# m1-ram.net
KiCad netlist of a schematic drawn in EAGLE
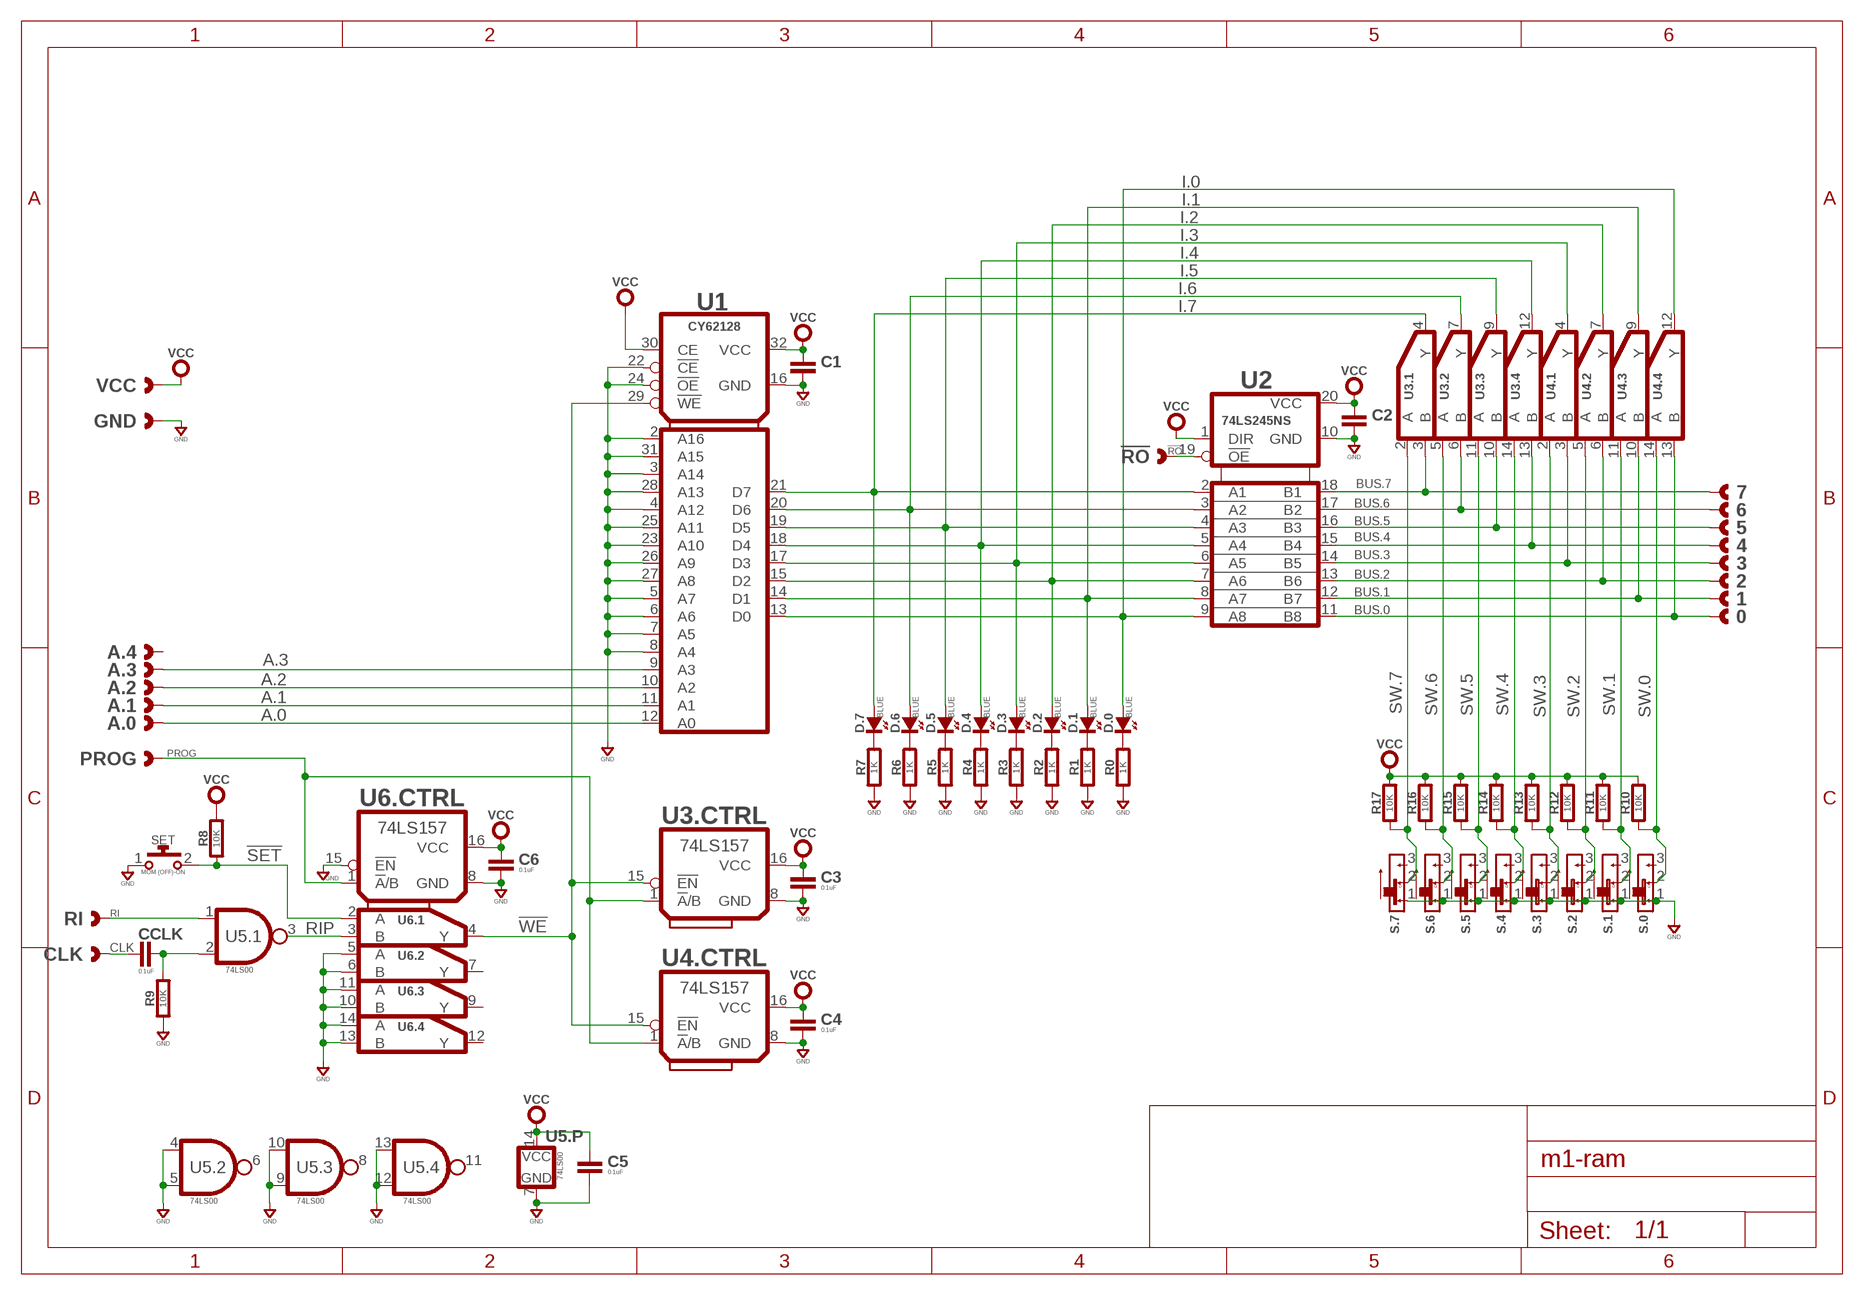
[diagram p0: schematic, sheet 1]

(export (version "E")
  (design (tool "Eeschema 10.0.6"))
  (components
    (comp (ref "!RO")
      (value "CAST-01X1")
      (footprint "eagle-import:CAST01-2.54MM")
      (libsource (lib "eagle-import") (part "CAST-01X1"))
    )
    (comp (ref "0")
      (value "CAST-01X1")
      (footprint "eagle-import:CAST01-2.54MM")
      (libsource (lib "eagle-import") (part "CAST-01X1"))
    )
    (comp (ref "1")
      (value "CAST-01X1")
      (footprint "eagle-import:CAST01-2.54MM")
      (libsource (lib "eagle-import") (part "CAST-01X1"))
    )
    (comp (ref "2")
      (value "CAST-01X1")
      (footprint "eagle-import:CAST01-2.54MM")
      (libsource (lib "eagle-import") (part "CAST-01X1"))
    )
    (comp (ref "3")
      (value "CAST-01X1")
      (footprint "eagle-import:CAST01-2.54MM")
      (libsource (lib "eagle-import") (part "CAST-01X1"))
    )
    (comp (ref "4")
      (value "CAST-01X1")
      (footprint "eagle-import:CAST01-2.54MM")
      (libsource (lib "eagle-import") (part "CAST-01X1"))
    )
    (comp (ref "5")
      (value "CAST-01X1")
      (footprint "eagle-import:CAST01-2.54MM")
      (libsource (lib "eagle-import") (part "CAST-01X1"))
    )
    (comp (ref "6")
      (value "CAST-01X1")
      (footprint "eagle-import:CAST01-2.54MM")
      (libsource (lib "eagle-import") (part "CAST-01X1"))
    )
    (comp (ref "7")
      (value "CAST-01X1")
      (footprint "eagle-import:CAST01-2.54MM")
      (libsource (lib "eagle-import") (part "CAST-01X1"))
    )
    (comp (ref "A.0")
      (value "CAST-01X1")
      (footprint "eagle-import:CAST01-2.54MM")
      (libsource (lib "eagle-import") (part "CAST-01X1"))
    )
    (comp (ref "A.1")
      (value "CAST-01X1")
      (footprint "eagle-import:CAST01-2.54MM")
      (libsource (lib "eagle-import") (part "CAST-01X1"))
    )
    (comp (ref "A.2")
      (value "CAST-01X1")
      (footprint "eagle-import:CAST01-2.54MM")
      (libsource (lib "eagle-import") (part "CAST-01X1"))
    )
    (comp (ref "A.3")
      (value "CAST-01X1")
      (footprint "eagle-import:CAST01-2.54MM")
      (libsource (lib "eagle-import") (part "CAST-01X1"))
    )
    (comp (ref "A.4")
      (value "CAST-01X1")
      (footprint "eagle-import:CAST01-2.54MM")
      (libsource (lib "eagle-import") (part "CAST-01X1"))
    )
    (comp (ref "C1")
      (value "CAPACITOR0603")
      (footprint "eagle-import:0603-CAP")
      (libsource (lib "eagle-import") (part "CAPACITOR0603"))
    )
    (comp (ref "C2")
      (value "CAPACITOR0603")
      (footprint "eagle-import:0603-CAP")
      (libsource (lib "eagle-import") (part "CAPACITOR0603"))
    )
    (comp (ref "C3")
      (value "0.1uF")
      (footprint "eagle-import:0603-CAP")
      (libsource (lib "eagle-import") (part "CAPACITOR0603"))
    )
    (comp (ref "C4")
      (value "0.1uF")
      (footprint "eagle-import:0603-CAP")
      (libsource (lib "eagle-import") (part "CAPACITOR0603"))
    )
    (comp (ref "C5")
      (value "0.1uF")
      (footprint "eagle-import:0603-CAP")
      (libsource (lib "eagle-import") (part "CAPACITOR0603"))
    )
    (comp (ref "C6")
      (value "0.1uF")
      (footprint "eagle-import:0603-CAP")
      (libsource (lib "eagle-import") (part "CAPACITOR0603"))
    )
    (comp (ref "CCLK")
      (value "0.1uF")
      (footprint "eagle-import:0603-CAP")
      (libsource (lib "eagle-import") (part "CAPACITOR0603"))
    )
    (comp (ref "CLK")
      (value "CAST-01X1")
      (footprint "eagle-import:CAST01-2.54MM")
      (libsource (lib "eagle-import") (part "CAST-01X1"))
    )
    (comp (ref "D.0")
      (value "BLUE")
      (footprint "eagle-import:SMD_0603")
      (libsource (lib "eagle-import") (part "SMT0603"))
    )
    (comp (ref "D.1")
      (value "BLUE")
      (footprint "eagle-import:SMD_0603")
      (libsource (lib "eagle-import") (part "SMT0603"))
    )
    (comp (ref "D.2")
      (value "BLUE")
      (footprint "eagle-import:SMD_0603")
      (libsource (lib "eagle-import") (part "SMT0603"))
    )
    (comp (ref "D.3")
      (value "BLUE")
      (footprint "eagle-import:SMD_0603")
      (libsource (lib "eagle-import") (part "SMT0603"))
    )
    (comp (ref "D.4")
      (value "BLUE")
      (footprint "eagle-import:SMD_0603")
      (libsource (lib "eagle-import") (part "SMT0603"))
    )
    (comp (ref "D.5")
      (value "BLUE")
      (footprint "eagle-import:SMD_0603")
      (libsource (lib "eagle-import") (part "SMT0603"))
    )
    (comp (ref "D.6")
      (value "BLUE")
      (footprint "eagle-import:SMD_0603")
      (libsource (lib "eagle-import") (part "SMT0603"))
    )
    (comp (ref "D.7")
      (value "BLUE")
      (footprint "eagle-import:SMD_0603")
      (libsource (lib "eagle-import") (part "SMT0603"))
    )
    (comp (ref "GND")
      (value "CAST-01X1")
      (footprint "eagle-import:CAST01-2.54MM")
      (libsource (lib "eagle-import") (part "CAST-01X1"))
    )
    (comp (ref "PROG")
      (value "CAST-01X1")
      (footprint "eagle-import:CAST01-2.54MM")
      (libsource (lib "eagle-import") (part "CAST-01X1"))
    )
    (comp (ref "R0")
      (value "1K")
      (footprint "eagle-import:0603-RES")
      (libsource (lib "eagle-import") (part "RESISTOR0603"))
    )
    (comp (ref "R1")
      (value "1K")
      (footprint "eagle-import:0603-RES")
      (libsource (lib "eagle-import") (part "RESISTOR0603"))
    )
    (comp (ref "R2")
      (value "1K")
      (footprint "eagle-import:0603-RES")
      (libsource (lib "eagle-import") (part "RESISTOR0603"))
    )
    (comp (ref "R3")
      (value "1K")
      (footprint "eagle-import:0603-RES")
      (libsource (lib "eagle-import") (part "RESISTOR0603"))
    )
    (comp (ref "R4")
      (value "1K")
      (footprint "eagle-import:0603-RES")
      (libsource (lib "eagle-import") (part "RESISTOR0603"))
    )
    (comp (ref "R5")
      (value "1K")
      (footprint "eagle-import:0603-RES")
      (libsource (lib "eagle-import") (part "RESISTOR0603"))
    )
    (comp (ref "R6")
      (value "1K")
      (footprint "eagle-import:0603-RES")
      (libsource (lib "eagle-import") (part "RESISTOR0603"))
    )
    (comp (ref "R7")
      (value "1K")
      (footprint "eagle-import:0603-RES")
      (libsource (lib "eagle-import") (part "RESISTOR0603"))
    )
    (comp (ref "R8")
      (value "10K")
      (footprint "eagle-import:0603-RES")
      (libsource (lib "eagle-import") (part "RESISTOR0603"))
    )
    (comp (ref "R9")
      (value "10K")
      (footprint "eagle-import:0603-RES")
      (libsource (lib "eagle-import") (part "RESISTOR0603"))
    )
    (comp (ref "R10")
      (value "10K")
      (footprint "eagle-import:0603-RES")
      (libsource (lib "eagle-import") (part "RESISTOR0603"))
    )
    (comp (ref "R11")
      (value "10K")
      (footprint "eagle-import:0603-RES")
      (libsource (lib "eagle-import") (part "RESISTOR0603"))
    )
    (comp (ref "R12")
      (value "10K")
      (footprint "eagle-import:0603-RES")
      (libsource (lib "eagle-import") (part "RESISTOR0603"))
    )
    (comp (ref "R13")
      (value "10K")
      (footprint "eagle-import:0603-RES")
      (libsource (lib "eagle-import") (part "RESISTOR0603"))
    )
    (comp (ref "R14")
      (value "10K")
      (footprint "eagle-import:0603-RES")
      (libsource (lib "eagle-import") (part "RESISTOR0603"))
    )
    (comp (ref "R15")
      (value "10K")
      (footprint "eagle-import:0603-RES")
      (libsource (lib "eagle-import") (part "RESISTOR0603"))
    )
    (comp (ref "R16")
      (value "10K")
      (footprint "eagle-import:0603-RES")
      (libsource (lib "eagle-import") (part "RESISTOR0603"))
    )
    (comp (ref "R17")
      (value "10K")
      (footprint "eagle-import:0603-RES")
      (libsource (lib "eagle-import") (part "RESISTOR0603"))
    )
    (comp (ref "RI")
      (value "CAST-01X1")
      (footprint "eagle-import:CAST01-2.54MM")
      (libsource (lib "eagle-import") (part "CAST-01X1"))
    )
    (comp (ref "S.0")
      (value "SLIDE-SPDTJS102011JCQN")
      (footprint "eagle-import:CK_JS102011JCQN")
      (libsource (lib "eagle-import") (part "SLIDE-SPDTJS102011JCQN"))
    )
    (comp (ref "S.1")
      (value "SLIDE-SPDTJS102011JCQN")
      (footprint "eagle-import:CK_JS102011JCQN")
      (libsource (lib "eagle-import") (part "SLIDE-SPDTJS102011JCQN"))
    )
    (comp (ref "S.2")
      (value "SLIDE-SPDTJS102011JCQN")
      (footprint "eagle-import:CK_JS102011JCQN")
      (libsource (lib "eagle-import") (part "SLIDE-SPDTJS102011JCQN"))
    )
    (comp (ref "S.3")
      (value "SLIDE-SPDTJS102011JCQN")
      (footprint "eagle-import:CK_JS102011JCQN")
      (libsource (lib "eagle-import") (part "SLIDE-SPDTJS102011JCQN"))
    )
    (comp (ref "S.4")
      (value "SLIDE-SPDTJS102011JCQN")
      (footprint "eagle-import:CK_JS102011JCQN")
      (libsource (lib "eagle-import") (part "SLIDE-SPDTJS102011JCQN"))
    )
    (comp (ref "S.5")
      (value "SLIDE-SPDTJS102011JCQN")
      (footprint "eagle-import:CK_JS102011JCQN")
      (libsource (lib "eagle-import") (part "SLIDE-SPDTJS102011JCQN"))
    )
    (comp (ref "S.6")
      (value "SLIDE-SPDTJS102011JCQN")
      (footprint "eagle-import:CK_JS102011JCQN")
      (libsource (lib "eagle-import") (part "SLIDE-SPDTJS102011JCQN"))
    )
    (comp (ref "S.7")
      (value "SLIDE-SPDTJS102011JCQN")
      (footprint "eagle-import:CK_JS102011JCQN")
      (libsource (lib "eagle-import") (part "SLIDE-SPDTJS102011JCQN"))
    )
    (comp (ref "SET")
      (value "MOM (OFF)-ON")
      (footprint "eagle-import:SWITCH-0635-2P-SMD")
      (fields (field (name "MFR") "CK Switch") (field (name "MPN") "PTS635S*SMTR"))
      (libsource (lib "eagle-import") (part "TACTILE-2PSMD"))
    )
    (comp (ref "U1")
      (value "CY62128")
      (footprint "eagle-import:SO32")
      (fields (field (name "MFR") "Cypress") (field (name "MPN") "CY62128ELL-45SXI"))
      (libsource (lib "eagle-import") (part "SRAM_128KX8CYPRESS"))
    )
    (comp (ref "U2")
      (value "74LS245NS")
      (footprint "eagle-import:SO20")
      (libsource (lib "eagle-import") (part "74245?NSLS"))
    )
    (comp (ref "U3")
      (value "74LS157")
      (footprint "eagle-import:SO16")
      (fields (field (name "MPN") "74LS157D"))
      (libsource (lib "eagle-import") (part "74157?DLS"))
    )
    (comp (ref "U4")
      (value "74LS157")
      (footprint "eagle-import:SO16")
      (fields (field (name "MPN") "74LS157D"))
      (libsource (lib "eagle-import") (part "74157?DLS"))
    )
    (comp (ref "U5")
      (value "74LS00")
      (footprint "eagle-import:SOP14")
      (fields (field (name "MPN") "74LS00N"))
      (libsource (lib "eagle-import") (part "7400?DLS"))
    )
    (comp (ref "U6")
      (value "74LS157")
      (footprint "eagle-import:SO16")
      (fields (field (name "MPN") "74LS157D"))
      (libsource (lib "eagle-import") (part "74157?DLS"))
    )
    (comp (ref "VCC")
      (value "CAST-01X1")
      (footprint "eagle-import:CAST01-2.54MM")
      (libsource (lib "eagle-import") (part "CAST-01X1"))
    )
  )
  (nets
    (net (code "1") (name "/A.0") (class "Default")
      (node (ref "A.0") (pin "1") (pinfunction "1_1") (pintype "bidirectional"))
      (node (ref "U1") (pin "12") (pinfunction "A0_12") (pintype "input"))
    )
    (net (code "2") (name "/A.1") (class "Default")
      (node (ref "A.1") (pin "1") (pinfunction "1_1") (pintype "bidirectional"))
      (node (ref "U1") (pin "11") (pinfunction "A1_11") (pintype "input"))
    )
    (net (code "3") (name "/A.2") (class "Default")
      (node (ref "A.2") (pin "1") (pinfunction "1_1") (pintype "bidirectional"))
      (node (ref "U1") (pin "10") (pinfunction "A2_10") (pintype "input"))
    )
    (net (code "4") (name "/A.3") (class "Default")
      (node (ref "A.3") (pin "1") (pinfunction "1_1") (pintype "bidirectional"))
      (node (ref "U1") (pin "9") (pinfunction "A3_9") (pintype "input"))
    )
    (net (code "5") (name "/BUS.0") (class "Default")
      (node (ref "0") (pin "1") (pinfunction "1_1") (pintype "bidirectional"))
      (node (ref "U2") (pin "11") (pinfunction "B8_11") (pintype "bidirectional"))
      (node (ref "U4") (pin "13") (pinfunction "B_13") (pintype "input"))
    )
    (net (code "6") (name "/BUS.1") (class "Default")
      (node (ref "1") (pin "1") (pinfunction "1_1") (pintype "bidirectional"))
      (node (ref "U2") (pin "12") (pinfunction "B7_12") (pintype "bidirectional"))
      (node (ref "U4") (pin "10") (pinfunction "B_10") (pintype "input"))
    )
    (net (code "7") (name "/BUS.2") (class "Default")
      (node (ref "2") (pin "1") (pinfunction "1_1") (pintype "bidirectional"))
      (node (ref "U2") (pin "13") (pinfunction "B6_13") (pintype "bidirectional"))
      (node (ref "U4") (pin "6") (pinfunction "B_6") (pintype "input"))
    )
    (net (code "8") (name "/BUS.3") (class "Default")
      (node (ref "3") (pin "1") (pinfunction "1_1") (pintype "bidirectional"))
      (node (ref "U2") (pin "14") (pinfunction "B5_14") (pintype "bidirectional"))
      (node (ref "U4") (pin "3") (pinfunction "B_3") (pintype "input"))
    )
    (net (code "9") (name "/BUS.4") (class "Default")
      (node (ref "4") (pin "1") (pinfunction "1_1") (pintype "bidirectional"))
      (node (ref "U2") (pin "15") (pinfunction "B4_15") (pintype "bidirectional"))
      (node (ref "U3") (pin "13") (pinfunction "B_13") (pintype "input"))
    )
    (net (code "10") (name "/BUS.5") (class "Default")
      (node (ref "5") (pin "1") (pinfunction "1_1") (pintype "bidirectional"))
      (node (ref "U2") (pin "16") (pinfunction "B3_16") (pintype "bidirectional"))
      (node (ref "U3") (pin "10") (pinfunction "B_10") (pintype "input"))
    )
    (net (code "11") (name "/BUS.6") (class "Default")
      (node (ref "6") (pin "1") (pinfunction "1_1") (pintype "bidirectional"))
      (node (ref "U2") (pin "17") (pinfunction "B2_17") (pintype "bidirectional"))
      (node (ref "U3") (pin "6") (pinfunction "B_6") (pintype "input"))
    )
    (net (code "12") (name "/BUS.7") (class "Default")
      (node (ref "7") (pin "1") (pinfunction "1_1") (pintype "bidirectional"))
      (node (ref "U2") (pin "18") (pinfunction "B1_18") (pintype "bidirectional"))
      (node (ref "U3") (pin "3") (pinfunction "B_3") (pintype "input"))
    )
    (net (code "13") (name "/CLK") (class "Default")
      (node (ref "CCLK") (pin "1") (pinfunction "1_1") (pintype "passive"))
      (node (ref "CLK") (pin "1") (pinfunction "1_1") (pintype "bidirectional"))
    )
    (net (code "14") (name "/I.0") (class "Default")
      (node (ref "D.0") (pin "A") (pinfunction "A_A") (pintype "passive"))
      (node (ref "U1") (pin "13") (pinfunction "D0_13") (pintype "bidirectional"))
      (node (ref "U2") (pin "9") (pinfunction "A8_9") (pintype "bidirectional"))
      (node (ref "U4") (pin "12") (pinfunction "Y_12") (pintype "output"))
    )
    (net (code "15") (name "/I.1") (class "Default")
      (node (ref "D.1") (pin "A") (pinfunction "A_A") (pintype "passive"))
      (node (ref "U1") (pin "14") (pinfunction "D1_14") (pintype "bidirectional"))
      (node (ref "U2") (pin "8") (pinfunction "A7_8") (pintype "bidirectional"))
      (node (ref "U4") (pin "9") (pinfunction "Y_9") (pintype "output"))
    )
    (net (code "16") (name "/I.2") (class "Default")
      (node (ref "D.2") (pin "A") (pinfunction "A_A") (pintype "passive"))
      (node (ref "U1") (pin "15") (pinfunction "D2_15") (pintype "bidirectional"))
      (node (ref "U2") (pin "7") (pinfunction "A6_7") (pintype "bidirectional"))
      (node (ref "U4") (pin "7") (pinfunction "Y_7") (pintype "output"))
    )
    (net (code "17") (name "/I.3") (class "Default")
      (node (ref "D.3") (pin "A") (pinfunction "A_A") (pintype "passive"))
      (node (ref "U1") (pin "17") (pinfunction "D3_17") (pintype "bidirectional"))
      (node (ref "U2") (pin "6") (pinfunction "A5_6") (pintype "bidirectional"))
      (node (ref "U4") (pin "4") (pinfunction "Y_4") (pintype "output"))
    )
    (net (code "18") (name "/I.4") (class "Default")
      (node (ref "D.4") (pin "A") (pinfunction "A_A") (pintype "passive"))
      (node (ref "U1") (pin "18") (pinfunction "D4_18") (pintype "bidirectional"))
      (node (ref "U2") (pin "5") (pinfunction "A4_5") (pintype "bidirectional"))
      (node (ref "U3") (pin "12") (pinfunction "Y_12") (pintype "output"))
    )
    (net (code "19") (name "/I.5") (class "Default")
      (node (ref "D.5") (pin "A") (pinfunction "A_A") (pintype "passive"))
      (node (ref "U1") (pin "19") (pinfunction "D5_19") (pintype "bidirectional"))
      (node (ref "U2") (pin "4") (pinfunction "A3_4") (pintype "bidirectional"))
      (node (ref "U3") (pin "9") (pinfunction "Y_9") (pintype "output"))
    )
    (net (code "20") (name "/I.6") (class "Default")
      (node (ref "D.6") (pin "A") (pinfunction "A_A") (pintype "passive"))
      (node (ref "U1") (pin "20") (pinfunction "D6_20") (pintype "bidirectional"))
      (node (ref "U2") (pin "3") (pinfunction "A2_3") (pintype "bidirectional"))
      (node (ref "U3") (pin "7") (pinfunction "Y_7") (pintype "output"))
    )
    (net (code "21") (name "/I.7") (class "Default")
      (node (ref "D.7") (pin "A") (pinfunction "A_A") (pintype "passive"))
      (node (ref "U1") (pin "21") (pinfunction "D7_21") (pintype "bidirectional"))
      (node (ref "U2") (pin "2") (pinfunction "A1_2") (pintype "bidirectional"))
      (node (ref "U3") (pin "4") (pinfunction "Y_4") (pintype "output"))
    )
    (net (code "22") (name "/PROG") (class "Default")
      (node (ref "PROG") (pin "1") (pinfunction "1_1") (pintype "bidirectional"))
      (node (ref "U3") (pin "1") (pinfunction "~{A}/B_1") (pintype "output"))
      (node (ref "U4") (pin "1") (pinfunction "~{A}/B_1") (pintype "output"))
      (node (ref "U6") (pin "1") (pinfunction "~{A}/B_1") (pintype "output"))
    )
    (net (code "23") (name "/RI") (class "Default")
      (node (ref "RI") (pin "1") (pinfunction "1_1") (pintype "bidirectional"))
      (node (ref "U5") (pin "1") (pinfunction "A_1") (pintype "input"))
    )
    (net (code "24") (name "/RIP") (class "Default")
      (node (ref "U5") (pin "3") (pinfunction "Y_3") (pintype "output"))
      (node (ref "U6") (pin "3") (pinfunction "B_3") (pintype "input"))
    )
    (net (code "25") (name "/SW.0") (class "Default")
      (node (ref "R10") (pin "1") (pinfunction "1_1") (pintype "passive"))
      (node (ref "S.0") (pin "2") (pinfunction "2_2") (pintype "bidirectional"))
      (node (ref "U4") (pin "14") (pinfunction "A_14") (pintype "input"))
    )
    (net (code "26") (name "/SW.1") (class "Default")
      (node (ref "R11") (pin "1") (pinfunction "1_1") (pintype "passive"))
      (node (ref "S.1") (pin "2") (pinfunction "2_2") (pintype "bidirectional"))
      (node (ref "U4") (pin "11") (pinfunction "A_11") (pintype "input"))
    )
    (net (code "27") (name "/SW.2") (class "Default")
      (node (ref "R12") (pin "1") (pinfunction "1_1") (pintype "passive"))
      (node (ref "S.2") (pin "2") (pinfunction "2_2") (pintype "bidirectional"))
      (node (ref "U4") (pin "5") (pinfunction "A_5") (pintype "input"))
    )
    (net (code "28") (name "/SW.3") (class "Default")
      (node (ref "R13") (pin "1") (pinfunction "1_1") (pintype "passive"))
      (node (ref "S.3") (pin "2") (pinfunction "2_2") (pintype "bidirectional"))
      (node (ref "U4") (pin "2") (pinfunction "A_2") (pintype "input"))
    )
    (net (code "29") (name "/SW.4") (class "Default")
      (node (ref "R14") (pin "1") (pinfunction "1_1") (pintype "passive"))
      (node (ref "S.4") (pin "2") (pinfunction "2_2") (pintype "bidirectional"))
      (node (ref "U3") (pin "14") (pinfunction "A_14") (pintype "input"))
    )
    (net (code "30") (name "/SW.5") (class "Default")
      (node (ref "R15") (pin "1") (pinfunction "1_1") (pintype "passive"))
      (node (ref "S.5") (pin "2") (pinfunction "2_2") (pintype "bidirectional"))
      (node (ref "U3") (pin "11") (pinfunction "A_11") (pintype "input"))
    )
    (net (code "31") (name "/SW.6") (class "Default")
      (node (ref "R16") (pin "1") (pinfunction "1_1") (pintype "passive"))
      (node (ref "S.6") (pin "2") (pinfunction "2_2") (pintype "bidirectional"))
      (node (ref "U3") (pin "5") (pinfunction "A_5") (pintype "input"))
    )
    (net (code "32") (name "/SW.7") (class "Default")
      (node (ref "R17") (pin "1") (pinfunction "1_1") (pintype "passive"))
      (node (ref "S.7") (pin "2") (pinfunction "2_2") (pintype "bidirectional"))
      (node (ref "U3") (pin "2") (pinfunction "A_2") (pintype "input"))
    )
    (net (code "33") (name "/~{RO}") (class "Default")
      (node (ref "!RO") (pin "1") (pinfunction "1_1") (pintype "bidirectional"))
      (node (ref "U2") (pin "19") (pinfunction "~{OE}_19") (pintype "bidirectional"))
    )
    (net (code "34") (name "/~{SET}") (class "Default")
      (node (ref "R8") (pin "1") (pinfunction "1_1") (pintype "passive"))
      (node (ref "SET") (pin "2") (pinfunction "2_2") (pintype "bidirectional"))
      (node (ref "U6") (pin "2") (pinfunction "A_2") (pintype "input"))
    )
    (net (code "35") (name "/~{WE}") (class "Default")
      (node (ref "U1") (pin "29") (pinfunction "~{WE}_29") (pintype "input"))
      (node (ref "U3") (pin "15") (pinfunction "~{EN}_15") (pintype "output"))
      (node (ref "U4") (pin "15") (pinfunction "~{EN}_15") (pintype "output"))
      (node (ref "U6") (pin "4") (pinfunction "Y_4") (pintype "output"))
    )
    (net (code "36") (name "GND") (class "Default")
      (node (ref "C1") (pin "2") (pinfunction "2_2") (pintype "passive"))
      (node (ref "C2") (pin "2") (pinfunction "2_2") (pintype "passive"))
      (node (ref "C3") (pin "2") (pinfunction "2_2") (pintype "passive"))
      (node (ref "C4") (pin "2") (pinfunction "2_2") (pintype "passive"))
      (node (ref "C5") (pin "2") (pinfunction "2_2") (pintype "passive"))
      (node (ref "C6") (pin "2") (pinfunction "2_2") (pintype "passive"))
      (node (ref "GND") (pin "1") (pinfunction "1_1") (pintype "bidirectional"))
      (node (ref "R0") (pin "1") (pinfunction "1_1") (pintype "passive"))
      (node (ref "R1") (pin "1") (pinfunction "1_1") (pintype "passive"))
      (node (ref "R2") (pin "1") (pinfunction "1_1") (pintype "passive"))
      (node (ref "R3") (pin "1") (pinfunction "1_1") (pintype "passive"))
      (node (ref "R4") (pin "1") (pinfunction "1_1") (pintype "passive"))
      (node (ref "R5") (pin "1") (pinfunction "1_1") (pintype "passive"))
      (node (ref "R6") (pin "1") (pinfunction "1_1") (pintype "passive"))
      (node (ref "R7") (pin "1") (pinfunction "1_1") (pintype "passive"))
      (node (ref "R9") (pin "1") (pinfunction "1_1") (pintype "passive"))
      (node (ref "S.0") (pin "1") (pinfunction "1_1") (pintype "bidirectional"))
      (node (ref "S.1") (pin "1") (pinfunction "1_1") (pintype "bidirectional"))
      (node (ref "S.2") (pin "1") (pinfunction "1_1") (pintype "bidirectional"))
      (node (ref "S.3") (pin "1") (pinfunction "1_1") (pintype "bidirectional"))
      (node (ref "S.4") (pin "1") (pinfunction "1_1") (pintype "bidirectional"))
      (node (ref "S.5") (pin "1") (pinfunction "1_1") (pintype "bidirectional"))
      (node (ref "S.6") (pin "1") (pinfunction "1_1") (pintype "bidirectional"))
      (node (ref "S.7") (pin "1") (pinfunction "1_1") (pintype "bidirectional"))
      (node (ref "SET") (pin "1") (pinfunction "1_1") (pintype "bidirectional"))
      (node (ref "U1") (pin "16") (pinfunction "GND_16") (pintype "power_in"))
      (node (ref "U1") (pin "2") (pinfunction "A16_2") (pintype "input"))
      (node (ref "U1") (pin "22") (pinfunction "~{CE}_22") (pintype "input"))
      (node (ref "U1") (pin "23") (pinfunction "A10_23") (pintype "input"))
      (node (ref "U1") (pin "24") (pinfunction "~{OE}_24") (pintype "input"))
      (node (ref "U1") (pin "25") (pinfunction "A11_25") (pintype "input"))
      (node (ref "U1") (pin "26") (pinfunction "A9_26") (pintype "input"))
      (node (ref "U1") (pin "27") (pinfunction "A8_27") (pintype "input"))
      (node (ref "U1") (pin "28") (pinfunction "A13_28") (pintype "input"))
      (node (ref "U1") (pin "3") (pinfunction "A14_3") (pintype "input"))
      (node (ref "U1") (pin "31") (pinfunction "A15_31") (pintype "input"))
      (node (ref "U1") (pin "4") (pinfunction "A12_4") (pintype "input"))
      (node (ref "U1") (pin "5") (pinfunction "A7_5") (pintype "input"))
      (node (ref "U1") (pin "6") (pinfunction "A6_6") (pintype "input"))
      (node (ref "U1") (pin "7") (pinfunction "A5_7") (pintype "input"))
      (node (ref "U1") (pin "8") (pinfunction "A4_8") (pintype "input"))
      (node (ref "U2") (pin "10") (pinfunction "GND_10") (pintype "bidirectional"))
      (node (ref "U3") (pin "8") (pinfunction "GND_8") (pintype "power_in"))
      (node (ref "U4") (pin "8") (pinfunction "GND_8") (pintype "power_in"))
      (node (ref "U5") (pin "10") (pinfunction "A_10") (pintype "input"))
      (node (ref "U5") (pin "12") (pinfunction "B_12") (pintype "input"))
      (node (ref "U5") (pin "13") (pinfunction "A_13") (pintype "input"))
      (node (ref "U5") (pin "4") (pinfunction "A_4") (pintype "input"))
      (node (ref "U5") (pin "5") (pinfunction "B_5") (pintype "input"))
      (node (ref "U5") (pin "7") (pinfunction "GND_7") (pintype "power_in"))
      (node (ref "U5") (pin "9") (pinfunction "B_9") (pintype "input"))
      (node (ref "U6") (pin "10") (pinfunction "B_10") (pintype "input"))
      (node (ref "U6") (pin "11") (pinfunction "A_11") (pintype "input"))
      (node (ref "U6") (pin "13") (pinfunction "B_13") (pintype "input"))
      (node (ref "U6") (pin "14") (pinfunction "A_14") (pintype "input"))
      (node (ref "U6") (pin "15") (pinfunction "~{EN}_15") (pintype "output"))
      (node (ref "U6") (pin "5") (pinfunction "A_5") (pintype "input"))
      (node (ref "U6") (pin "6") (pinfunction "B_6") (pintype "input"))
      (node (ref "U6") (pin "8") (pinfunction "GND_8") (pintype "power_in"))
    )
    (net (code "37") (name "Net-(D.0-C)") (class "Default")
      (node (ref "D.0") (pin "K") (pinfunction "C_K") (pintype "passive"))
      (node (ref "R0") (pin "2") (pinfunction "2_2") (pintype "passive"))
    )
    (net (code "38") (name "Net-(D.1-C)") (class "Default")
      (node (ref "D.1") (pin "K") (pinfunction "C_K") (pintype "passive"))
      (node (ref "R1") (pin "2") (pinfunction "2_2") (pintype "passive"))
    )
    (net (code "39") (name "Net-(D.2-C)") (class "Default")
      (node (ref "D.2") (pin "K") (pinfunction "C_K") (pintype "passive"))
      (node (ref "R2") (pin "2") (pinfunction "2_2") (pintype "passive"))
    )
    (net (code "40") (name "Net-(D.3-C)") (class "Default")
      (node (ref "D.3") (pin "K") (pinfunction "C_K") (pintype "passive"))
      (node (ref "R3") (pin "2") (pinfunction "2_2") (pintype "passive"))
    )
    (net (code "41") (name "Net-(D.4-C)") (class "Default")
      (node (ref "D.4") (pin "K") (pinfunction "C_K") (pintype "passive"))
      (node (ref "R4") (pin "2") (pinfunction "2_2") (pintype "passive"))
    )
    (net (code "42") (name "Net-(D.5-C)") (class "Default")
      (node (ref "D.5") (pin "K") (pinfunction "C_K") (pintype "passive"))
      (node (ref "R5") (pin "2") (pinfunction "2_2") (pintype "passive"))
    )
    (net (code "43") (name "Net-(D.6-C)") (class "Default")
      (node (ref "D.6") (pin "K") (pinfunction "C_K") (pintype "passive"))
      (node (ref "R6") (pin "2") (pinfunction "2_2") (pintype "passive"))
    )
    (net (code "44") (name "Net-(D.7-C)") (class "Default")
      (node (ref "D.7") (pin "K") (pinfunction "C_K") (pintype "passive"))
      (node (ref "R7") (pin "2") (pinfunction "2_2") (pintype "passive"))
    )
    (net (code "45") (name "Net-(U5A-B)") (class "Default")
      (node (ref "CCLK") (pin "2") (pinfunction "2_2") (pintype "passive"))
      (node (ref "R9") (pin "2") (pinfunction "2_2") (pintype "passive"))
      (node (ref "U5") (pin "2") (pinfunction "B_2") (pintype "input"))
    )
    (net (code "46") (name "VCC") (class "Default")
      (node (ref "C1") (pin "1") (pinfunction "1_1") (pintype "passive"))
      (node (ref "C2") (pin "1") (pinfunction "1_1") (pintype "passive"))
      (node (ref "C3") (pin "1") (pinfunction "1_1") (pintype "passive"))
      (node (ref "C4") (pin "1") (pinfunction "1_1") (pintype "passive"))
      (node (ref "C5") (pin "1") (pinfunction "1_1") (pintype "passive"))
      (node (ref "C6") (pin "1") (pinfunction "1_1") (pintype "passive"))
      (node (ref "R10") (pin "2") (pinfunction "2_2") (pintype "passive"))
      (node (ref "R11") (pin "2") (pinfunction "2_2") (pintype "passive"))
      (node (ref "R12") (pin "2") (pinfunction "2_2") (pintype "passive"))
      (node (ref "R13") (pin "2") (pinfunction "2_2") (pintype "passive"))
      (node (ref "R14") (pin "2") (pinfunction "2_2") (pintype "passive"))
      (node (ref "R15") (pin "2") (pinfunction "2_2") (pintype "passive"))
      (node (ref "R16") (pin "2") (pinfunction "2_2") (pintype "passive"))
      (node (ref "R17") (pin "2") (pinfunction "2_2") (pintype "passive"))
      (node (ref "R8") (pin "2") (pinfunction "2_2") (pintype "passive"))
      (node (ref "U1") (pin "30") (pinfunction "CE_30") (pintype "input"))
      (node (ref "U1") (pin "32") (pinfunction "VCC_32") (pintype "power_in"))
      (node (ref "U2") (pin "1") (pinfunction "DIR_1") (pintype "bidirectional"))
      (node (ref "U2") (pin "20") (pinfunction "VCC_20") (pintype "bidirectional"))
      (node (ref "U3") (pin "16") (pinfunction "VCC_16") (pintype "power_in"))
      (node (ref "U4") (pin "16") (pinfunction "VCC_16") (pintype "power_in"))
      (node (ref "U5") (pin "14") (pinfunction "VCC_14") (pintype "power_in"))
      (node (ref "U6") (pin "16") (pinfunction "VCC_16") (pintype "power_in"))
      (node (ref "VCC") (pin "1") (pinfunction "1_1") (pintype "bidirectional"))
    )
    (net (code "47") (name "unconnected-(A.4-Pad1)") (class "Default")
      (node (ref "A.4") (pin "1") (pinfunction "1_1") (pintype "bidirectional"))
    )
    (net (code "48") (name "unconnected-(S.0-Pad3)") (class "Default")
      (node (ref "S.0") (pin "3") (pinfunction "3_3") (pintype "bidirectional"))
    )
    (net (code "49") (name "unconnected-(S.1-Pad3)") (class "Default")
      (node (ref "S.1") (pin "3") (pinfunction "3_3") (pintype "bidirectional"))
    )
    (net (code "50") (name "unconnected-(S.2-Pad3)") (class "Default")
      (node (ref "S.2") (pin "3") (pinfunction "3_3") (pintype "bidirectional"))
    )
    (net (code "51") (name "unconnected-(S.3-Pad3)") (class "Default")
      (node (ref "S.3") (pin "3") (pinfunction "3_3") (pintype "bidirectional"))
    )
    (net (code "52") (name "unconnected-(S.4-Pad3)") (class "Default")
      (node (ref "S.4") (pin "3") (pinfunction "3_3") (pintype "bidirectional"))
    )
    (net (code "53") (name "unconnected-(S.5-Pad3)") (class "Default")
      (node (ref "S.5") (pin "3") (pinfunction "3_3") (pintype "bidirectional"))
    )
    (net (code "54") (name "unconnected-(S.6-Pad3)") (class "Default")
      (node (ref "S.6") (pin "3") (pinfunction "3_3") (pintype "bidirectional"))
    )
    (net (code "55") (name "unconnected-(S.7-Pad3)") (class "Default")
      (node (ref "S.7") (pin "3") (pinfunction "3_3") (pintype "bidirectional"))
    )
    (net (code "56") (name "unconnected-(U5B-Y-Pad6)") (class "Default")
      (node (ref "U5") (pin "6") (pinfunction "Y_6") (pintype "output"))
    )
    (net (code "57") (name "unconnected-(U5C-Y-Pad8)") (class "Default")
      (node (ref "U5") (pin "8") (pinfunction "Y_8") (pintype "output"))
    )
    (net (code "58") (name "unconnected-(U5D-Y-Pad11)") (class "Default")
      (node (ref "U5") (pin "11") (pinfunction "Y_11") (pintype "output"))
    )
    (net (code "59") (name "unconnected-(U6B-Y-Pad7)") (class "Default")
      (node (ref "U6") (pin "7") (pinfunction "Y_7") (pintype "output"))
    )
    (net (code "60") (name "unconnected-(U6C-Y-Pad9)") (class "Default")
      (node (ref "U6") (pin "9") (pinfunction "Y_9") (pintype "output"))
    )
    (net (code "61") (name "unconnected-(U6D-Y-Pad12)") (class "Default")
      (node (ref "U6") (pin "12") (pinfunction "Y_12") (pintype "output"))
    )
  )
)
